# Power_Distribution_12_v.net
KiCad netlist of a schematic drawn in EAGLE
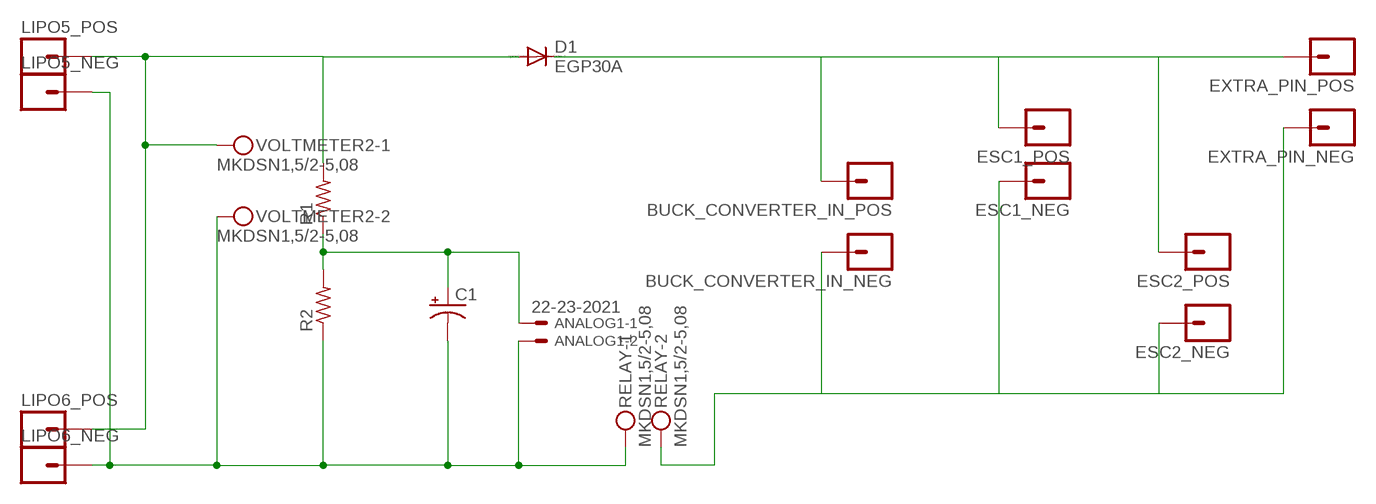
[diagram p0: schematic, sheet 1]

(export (version "E")
  (design (tool "Eeschema 10.0.6"))
  (components
    (comp (ref "ANALOG1")
      (value "22-23-2021")
      (footprint "eagle-import:22-23-2021")
      (fields (field (name "MF") "MOLEX"))
      (libsource (lib "eagle-import") (part "22-23-2021"))
    )
    (comp (ref "BUCK_CONVERTER_IN_NEG")
      (value "M01PTH_2MM")
      (footprint "eagle-import:1X01_2MM")
      (libsource (lib "eagle-import") (part "M01PTH_2MM"))
    )
    (comp (ref "BUCK_CONVERTER_IN_POS")
      (value "M01PTH_2MM")
      (footprint "eagle-import:1X01_2MM")
      (libsource (lib "eagle-import") (part "M01PTH_2MM"))
    )
    (comp (ref "C1")
      (value "CPOL-USE2-5")
      (footprint "eagle-import:E2-5")
      (libsource (lib "eagle-import") (part "CPOL-USE2-5"))
    )
    (comp (ref "D1")
      (value "EGP30A")
      (footprint "eagle-import:DO201-15")
      (libsource (lib "eagle-import") (part "EGP30A"))
    )
    (comp (ref "ESC1_NEG")
      (value "M01PTH_2MM")
      (footprint "eagle-import:1X01_2MM")
      (libsource (lib "eagle-import") (part "M01PTH_2MM"))
    )
    (comp (ref "ESC1_POS")
      (value "M01PTH_2MM")
      (footprint "eagle-import:1X01_2MM")
      (libsource (lib "eagle-import") (part "M01PTH_2MM"))
    )
    (comp (ref "ESC2_NEG")
      (value "M01PTH_2MM")
      (footprint "eagle-import:1X01_2MM")
      (libsource (lib "eagle-import") (part "M01PTH_2MM"))
    )
    (comp (ref "ESC2_POS")
      (value "M01PTH_2MM")
      (footprint "eagle-import:1X01_2MM")
      (libsource (lib "eagle-import") (part "M01PTH_2MM"))
    )
    (comp (ref "EXTRA_PIN_NEG")
      (value "M01PTH_2MM")
      (footprint "eagle-import:1X01_2MM")
      (libsource (lib "eagle-import") (part "M01PTH_2MM"))
    )
    (comp (ref "EXTRA_PIN_POS")
      (value "M01PTH_2MM")
      (footprint "eagle-import:1X01_2MM")
      (libsource (lib "eagle-import") (part "M01PTH_2MM"))
    )
    (comp (ref "LIPO5_NEG")
      (value "M01PTH_2MM")
      (footprint "eagle-import:1X01_2MM")
      (libsource (lib "eagle-import") (part "M01PTH_2MM"))
    )
    (comp (ref "LIPO5_POS")
      (value "M01PTH_2MM")
      (footprint "eagle-import:1X01_2MM")
      (libsource (lib "eagle-import") (part "M01PTH_2MM"))
    )
    (comp (ref "LIPO6_NEG")
      (value "M01PTH_2MM")
      (footprint "eagle-import:1X01_2MM")
      (libsource (lib "eagle-import") (part "M01PTH_2MM"))
    )
    (comp (ref "LIPO6_POS")
      (value "M01PTH_2MM")
      (footprint "eagle-import:1X01_2MM")
      (libsource (lib "eagle-import") (part "M01PTH_2MM"))
    )
    (comp (ref "R1")
      (value "R-US_0207/10")
      (footprint "eagle-import:0207_10")
      (libsource (lib "eagle-import") (part "R-US_0207/10"))
    )
    (comp (ref "R2")
      (value "R-US_0207/10")
      (footprint "eagle-import:0207_10")
      (libsource (lib "eagle-import") (part "R-US_0207/10"))
    )
    (comp (ref "RELAY")
      (value "MKDSN1,5/2-5,08")
      (footprint "eagle-import:MKDSN1,5_2-5,08")
      (libsource (lib "eagle-import") (part "MKDSN1,5/2-5,08"))
    )
    (comp (ref "VOLTMETER2")
      (value "MKDSN1,5/2-5,08")
      (footprint "eagle-import:MKDSN1,5_2-5,08")
      (libsource (lib "eagle-import") (part "MKDSN1,5/2-5,08"))
    )
  )
  (nets
    (net (code "1") (name "Net-(ANALOG1A-S)") (class "Default")
      (node (ref "ANALOG1") (pin "1") (pinfunction "S_1") (pintype "passive"))
      (node (ref "C1") (pin "+") (pinfunction "+_+") (pintype "passive"))
      (node (ref "R1") (pin "1") (pinfunction "1_1") (pintype "passive"))
      (node (ref "R2") (pin "2") (pinfunction "2_2") (pintype "passive"))
    )
    (net (code "2") (name "Net-(ANALOG1B-S)") (class "Default")
      (node (ref "ANALOG1") (pin "2") (pinfunction "S_2") (pintype "passive"))
      (node (ref "C1") (pin "-") (pinfunction "-_-") (pintype "passive"))
      (node (ref "LIPO5_NEG") (pin "1") (pinfunction "1_1") (pintype "passive"))
      (node (ref "LIPO6_NEG") (pin "1") (pinfunction "1_1") (pintype "passive"))
      (node (ref "R2") (pin "1") (pinfunction "1_1") (pintype "passive"))
      (node (ref "RELAY") (pin "1") (pinfunction "KL_1") (pintype "passive"))
      (node (ref "VOLTMETER2") (pin "2") (pinfunction "KL_2") (pintype "passive"))
    )
    (net (code "3") (name "Net-(BUCK_CONVERTER_IN_POS-Pad1)") (class "Default")
      (node (ref "BUCK_CONVERTER_IN_POS") (pin "1") (pinfunction "1_1") (pintype "passive"))
      (node (ref "D1") (pin "C") (pinfunction "C_C") (pintype "passive"))
      (node (ref "ESC1_POS") (pin "1") (pinfunction "1_1") (pintype "passive"))
      (node (ref "ESC2_POS") (pin "1") (pinfunction "1_1") (pintype "passive"))
      (node (ref "EXTRA_PIN_POS") (pin "1") (pinfunction "1_1") (pintype "passive"))
    )
    (net (code "4") (name "Net-(RELAYB-KL)") (class "Default")
      (node (ref "BUCK_CONVERTER_IN_NEG") (pin "1") (pinfunction "1_1") (pintype "passive"))
      (node (ref "ESC1_NEG") (pin "1") (pinfunction "1_1") (pintype "passive"))
      (node (ref "ESC2_NEG") (pin "1") (pinfunction "1_1") (pintype "passive"))
      (node (ref "EXTRA_PIN_NEG") (pin "1") (pinfunction "1_1") (pintype "passive"))
      (node (ref "RELAY") (pin "2") (pinfunction "KL_2") (pintype "passive"))
    )
    (net (code "5") (name "Net-(VOLTMETER2A-KL)") (class "Default")
      (node (ref "D1") (pin "A") (pinfunction "A_A") (pintype "passive"))
      (node (ref "LIPO5_POS") (pin "1") (pinfunction "1_1") (pintype "passive"))
      (node (ref "LIPO6_POS") (pin "1") (pinfunction "1_1") (pintype "passive"))
      (node (ref "R1") (pin "2") (pinfunction "2_2") (pintype "passive"))
      (node (ref "VOLTMETER2") (pin "1") (pinfunction "KL_1") (pintype "passive"))
    )
  )
)
